# SRX-dataport-breakout.net
KiCad netlist of a schematic drawn in EAGLE
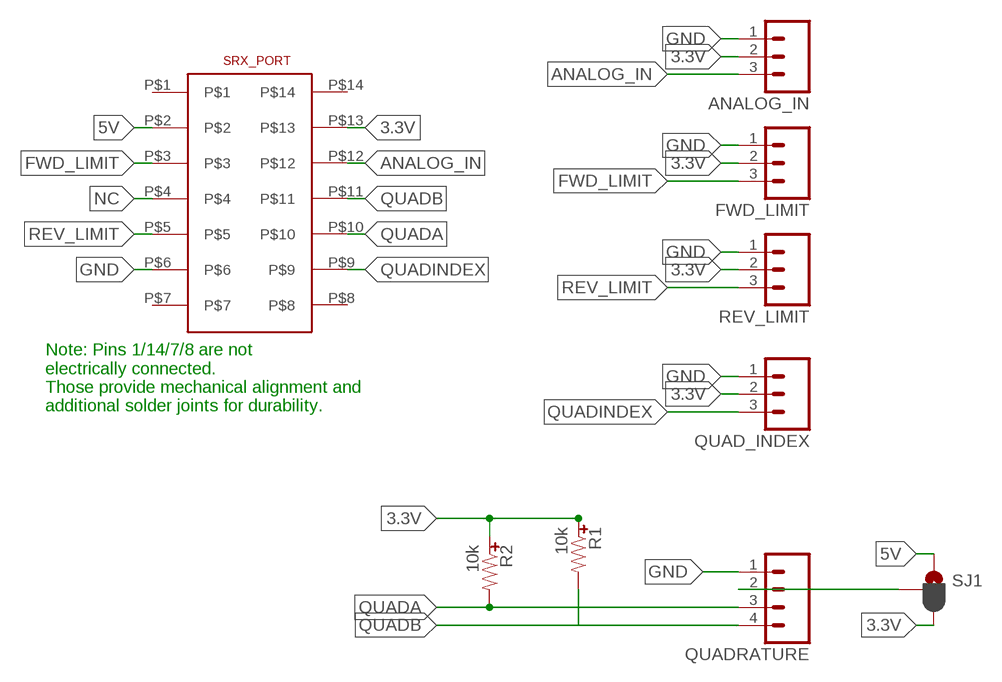
[diagram p0: schematic, sheet 1]

(export (version "E")
  (design (tool "Eeschema 10.0.6"))
  (components
    (comp (ref "ANALOG_IN")
      (value "M03LOCK")
      (footprint "eagle-import:1X03_LOCK")
      (libsource (lib "eagle-import") (part "M03LOCK"))
    )
    (comp (ref "FWD_LIMIT")
      (value "M03LOCK")
      (footprint "eagle-import:1X03_LOCK")
      (libsource (lib "eagle-import") (part "M03LOCK"))
    )
    (comp (ref "QUADRATURE")
      (value "M04LOCK")
      (footprint "eagle-import:1X04_LOCK")
      (libsource (lib "eagle-import") (part "M04LOCK"))
    )
    (comp (ref "QUAD_INDEX")
      (value "M03LOCK")
      (footprint "eagle-import:1X03_LOCK")
      (libsource (lib "eagle-import") (part "M03LOCK"))
    )
    (comp (ref "R1")
      (value "10k")
      (footprint "eagle-import:0402-0603-0805-UNIVERSAL")
      (libsource (lib "eagle-import") (part "RESISTORUNIVERSAL"))
    )
    (comp (ref "R2")
      (value "10k")
      (footprint "eagle-import:0402-0603-0805-UNIVERSAL")
      (libsource (lib "eagle-import") (part "RESISTORUNIVERSAL"))
    )
    (comp (ref "REV_LIMIT")
      (value "M03LOCK")
      (footprint "eagle-import:1X03_LOCK")
      (libsource (lib "eagle-import") (part "M03LOCK"))
    )
    (comp (ref "SJ1")
      (value "JUMPER-PAD-3-2OF3_NC_BY_PASTE")
      (footprint "eagle-import:PAD-JUMPER-3-2OF3_NC_BY_PASTE_YES_SILK_FULL_BOX")
      (libsource (lib "eagle-import") (part "JUMPER-PAD-3-2OF3_NC_BY_PASTE"))
    )
    (comp (ref "SRX_PORT")
      (value "M07X0220021321-00014TFLF")
      (footprint "eagle-import:M2X07_SMD")
      (libsource (lib "eagle-import") (part "M07X0220021321-00014TFLF"))
    )
  )
  (nets
    (net (code "1") (name "3.3V") (class "Default")
      (node (ref "ANALOG_IN") (pin "2") (pinfunction "2_2") (pintype "passive"))
      (node (ref "FWD_LIMIT") (pin "2") (pinfunction "2_2") (pintype "passive"))
      (node (ref "QUAD_INDEX") (pin "2") (pinfunction "2_2") (pintype "passive"))
      (node (ref "R1") (pin "+") (pinfunction "1_+") (pintype "passive"))
      (node (ref "R2") (pin "+") (pinfunction "1_+") (pintype "passive"))
      (node (ref "REV_LIMIT") (pin "2") (pinfunction "2_2") (pintype "passive"))
      (node (ref "SJ1") (pin "3") (pinfunction "3_3") (pintype "passive"))
      (node (ref "SRX_PORT") (pin "P$13") (pinfunction "P$13_P$13") (pintype "bidirectional"))
    )
    (net (code "2") (name "5V") (class "Default")
      (node (ref "SJ1") (pin "1") (pinfunction "1_1") (pintype "passive"))
      (node (ref "SRX_PORT") (pin "P$2") (pinfunction "P$2_P$2") (pintype "bidirectional"))
    )
    (net (code "3") (name "ANALOG_IN") (class "Default")
      (node (ref "ANALOG_IN") (pin "3") (pinfunction "3_3") (pintype "passive"))
      (node (ref "SRX_PORT") (pin "P$12") (pinfunction "P$12_P$12") (pintype "bidirectional"))
    )
    (net (code "4") (name "FWD_LIMIT") (class "Default")
      (node (ref "FWD_LIMIT") (pin "3") (pinfunction "3_3") (pintype "passive"))
      (node (ref "SRX_PORT") (pin "P$3") (pinfunction "P$3_P$3") (pintype "bidirectional"))
    )
    (net (code "5") (name "GND") (class "Default")
      (node (ref "ANALOG_IN") (pin "1") (pinfunction "1_1") (pintype "passive"))
      (node (ref "FWD_LIMIT") (pin "1") (pinfunction "1_1") (pintype "passive"))
      (node (ref "QUADRATURE") (pin "1") (pinfunction "1_1") (pintype "passive"))
      (node (ref "QUAD_INDEX") (pin "1") (pinfunction "1_1") (pintype "passive"))
      (node (ref "REV_LIMIT") (pin "1") (pinfunction "1_1") (pintype "passive"))
      (node (ref "SRX_PORT") (pin "P$6") (pinfunction "P$6_P$6") (pintype "bidirectional"))
    )
    (net (code "6") (name "NC") (class "Default")
      (node (ref "SRX_PORT") (pin "P$4") (pinfunction "P$4_P$4") (pintype "bidirectional"))
    )
    (net (code "7") (name "Net-(QUADRATURE-Pad2)") (class "Default")
      (node (ref "QUADRATURE") (pin "2") (pinfunction "2_2") (pintype "passive"))
      (node (ref "SJ1") (pin "2") (pinfunction "2_2") (pintype "passive"))
    )
    (net (code "8") (name "QUADA") (class "Default")
      (node (ref "QUADRATURE") (pin "3") (pinfunction "3_3") (pintype "passive"))
      (node (ref "R2") (pin "-") (pinfunction "2_-") (pintype "passive"))
      (node (ref "SRX_PORT") (pin "P$10") (pinfunction "P$10_P$10") (pintype "bidirectional"))
    )
    (net (code "9") (name "QUADB") (class "Default")
      (node (ref "QUADRATURE") (pin "4") (pinfunction "4_4") (pintype "passive"))
      (node (ref "R1") (pin "-") (pinfunction "2_-") (pintype "passive"))
      (node (ref "SRX_PORT") (pin "P$11") (pinfunction "P$11_P$11") (pintype "bidirectional"))
    )
    (net (code "10") (name "QUADINDEX") (class "Default")
      (node (ref "QUAD_INDEX") (pin "3") (pinfunction "3_3") (pintype "passive"))
      (node (ref "SRX_PORT") (pin "P$9") (pinfunction "P$9_P$9") (pintype "bidirectional"))
    )
    (net (code "11") (name "REV_LIMIT") (class "Default")
      (node (ref "REV_LIMIT") (pin "3") (pinfunction "3_3") (pintype "passive"))
      (node (ref "SRX_PORT") (pin "P$5") (pinfunction "P$5_P$5") (pintype "bidirectional"))
    )
    (net (code "12") (name "unconnected-(SRX_PORT-PadP$1)") (class "Default")
      (node (ref "SRX_PORT") (pin "P$1") (pinfunction "P$1_P$1") (pintype "bidirectional"))
    )
    (net (code "13") (name "unconnected-(SRX_PORT-PadP$7)") (class "Default")
      (node (ref "SRX_PORT") (pin "P$7") (pinfunction "P$7_P$7") (pintype "bidirectional"))
    )
    (net (code "14") (name "unconnected-(SRX_PORT-PadP$8)") (class "Default")
      (node (ref "SRX_PORT") (pin "P$8") (pinfunction "P$8_P$8") (pintype "bidirectional"))
    )
    (net (code "15") (name "unconnected-(SRX_PORT-PadP$14)") (class "Default")
      (node (ref "SRX_PORT") (pin "P$14") (pinfunction "P$14_P$14") (pintype "bidirectional"))
    )
  )
)
